# SCH_595__2023-01-18.net
KiCad netlist of a schematic drawn in EasyEDA
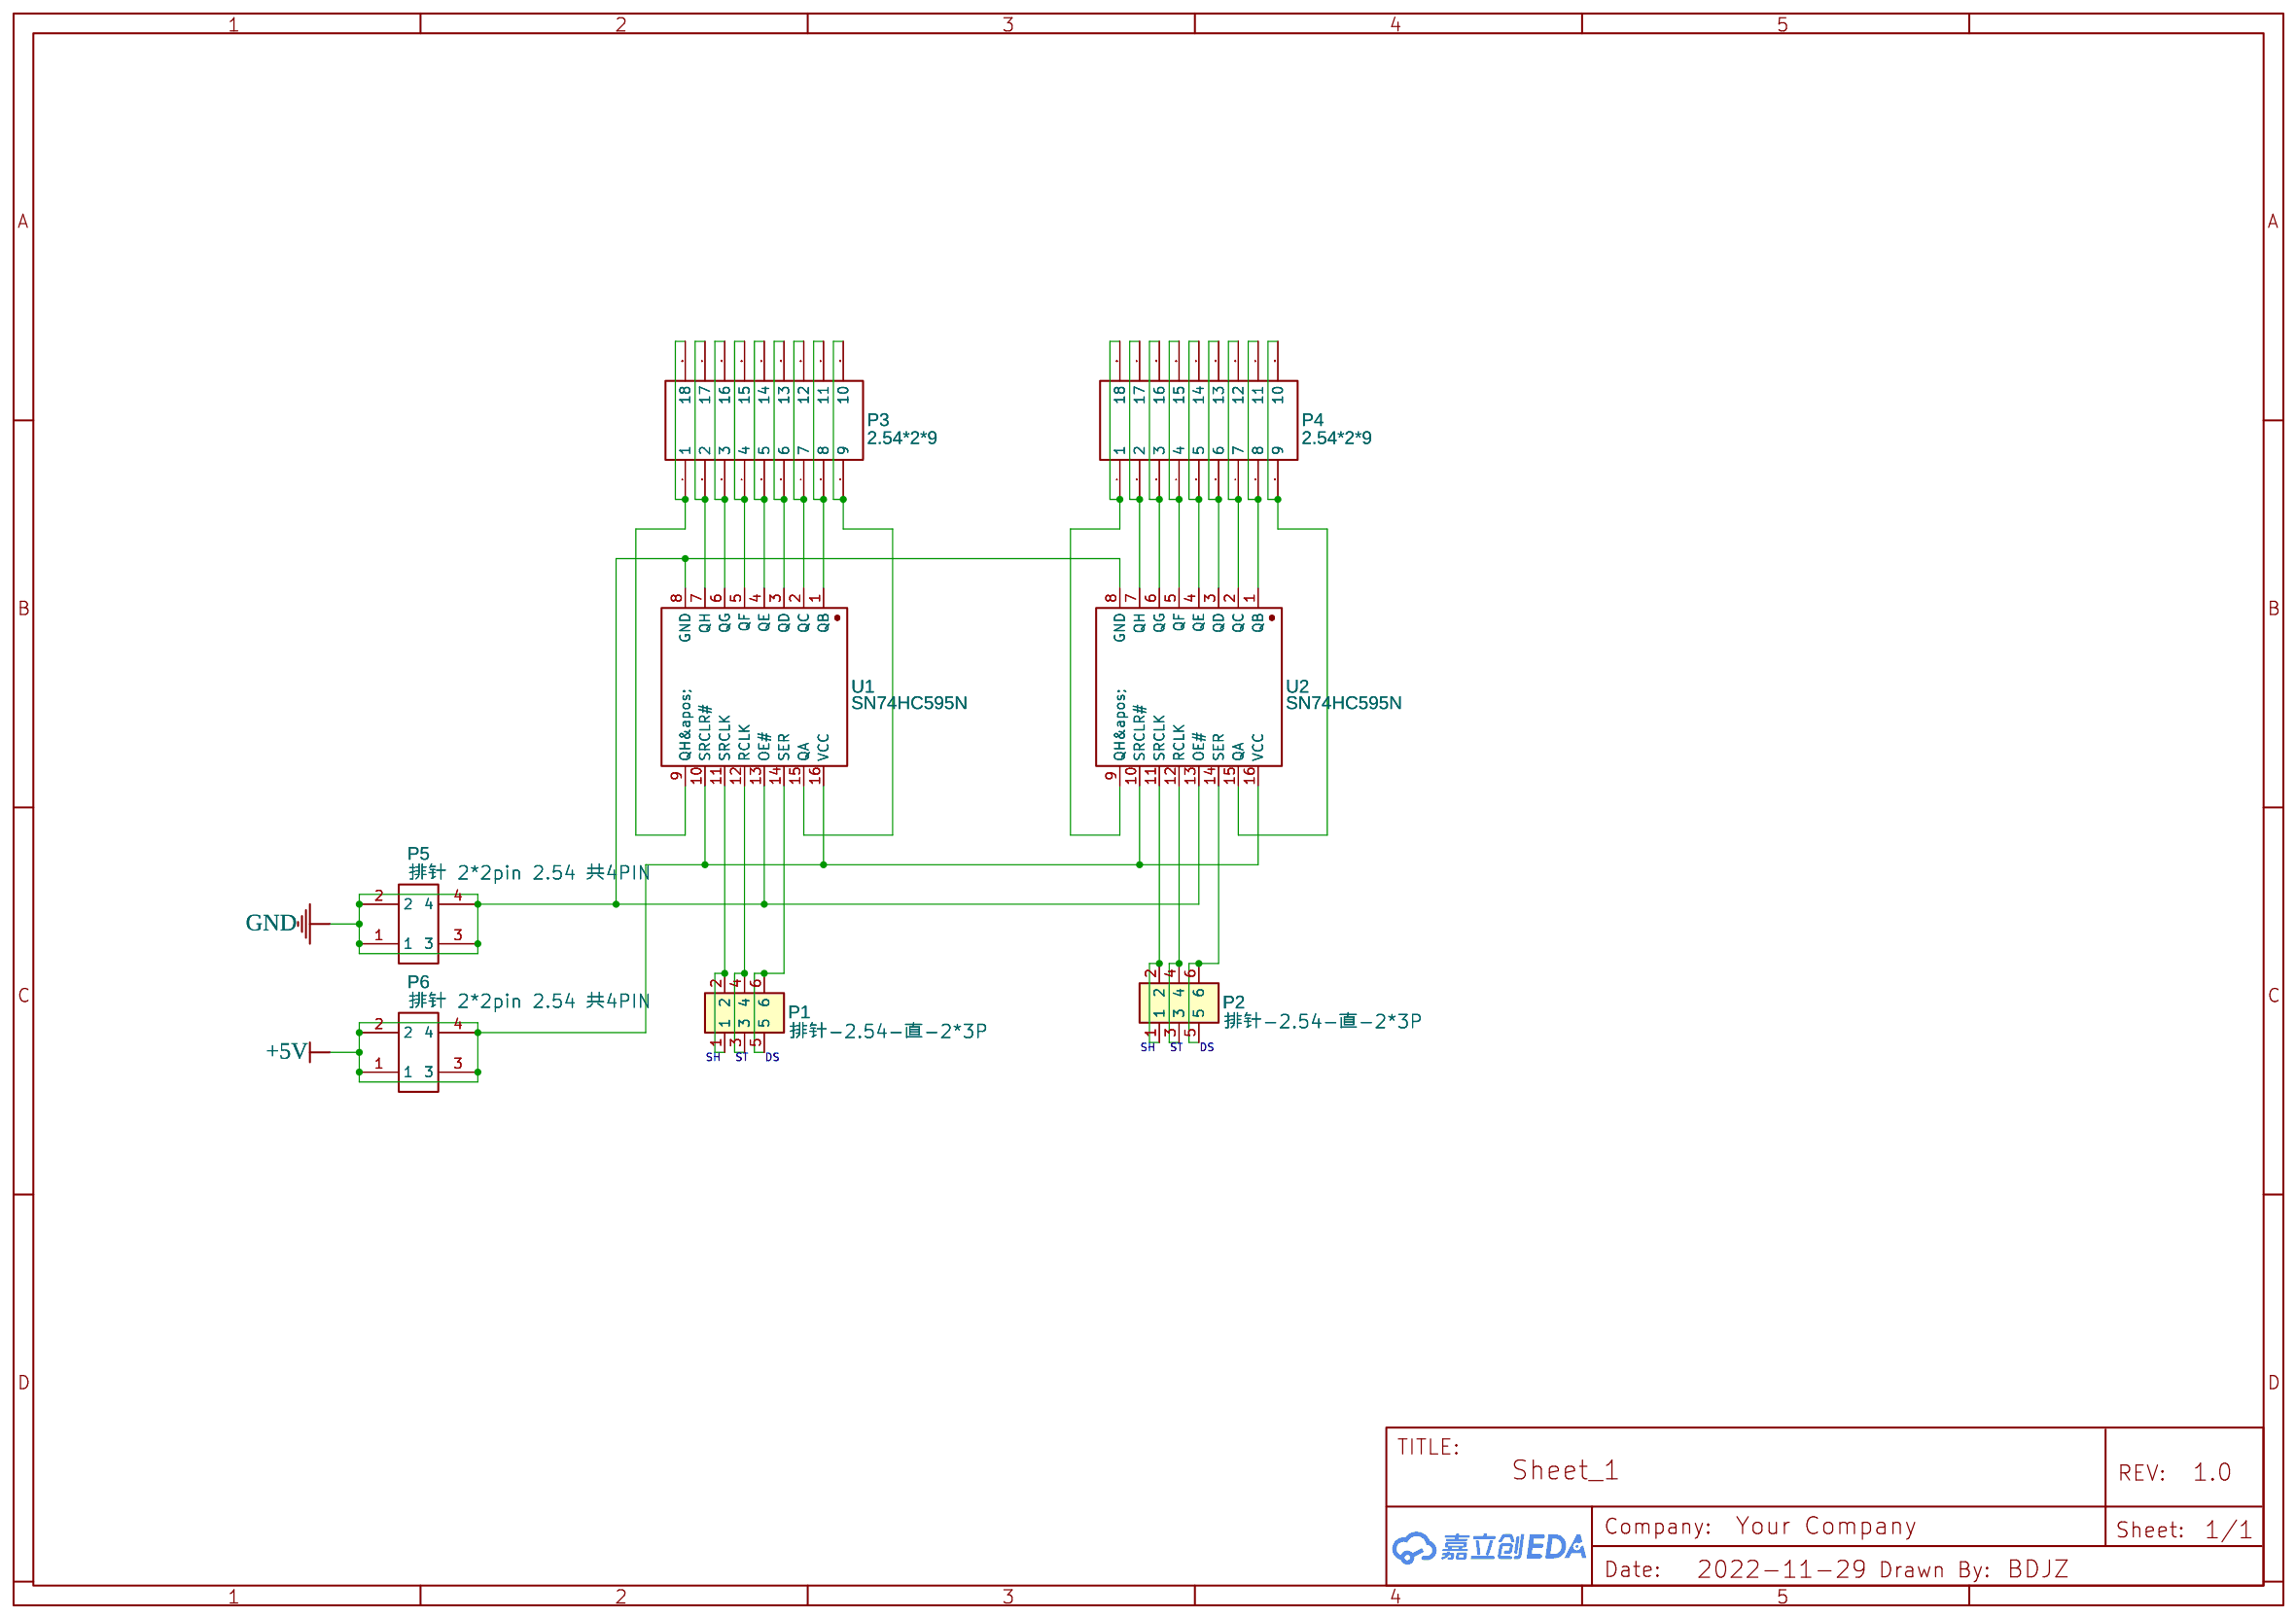
[diagram p0: schematic sheet]

(export (version "E")
  (design (tool "Eeschema 10.0.6"))
  (components
    (comp (ref "P1") (value "排针-2.54-直-2*3P") (libsource (lib "") (part "排针-2.54-直-2*3P")))
    (comp (ref "P2") (value "排针-2.54-直-2*3P") (libsource (lib "") (part "排针-2.54-直-2*3P")))
    (comp (ref "P3")
      (value "2.54*2*9")
      (fields (field (name "BOM_Supplier Part") "C115247"))
      (libsource (lib "") (part "2.54*2*9"))
    )
    (comp (ref "P4")
      (value "2.54*2*9")
      (fields (field (name "BOM_Supplier Part") "C115247"))
      (libsource (lib "") (part "2.54*2*9"))
    )
    (comp (ref "P5") (value "排针 2*2pin 2.54 共4PIN") (libsource (lib "") (part "排针 2*2pin 2.54 共4PIN")))
    (comp (ref "P6") (value "排针 2*2pin 2.54 共4PIN") (libsource (lib "") (part "排针 2*2pin 2.54 共4PIN")))
    (comp (ref "U1")
      (value "SN74HC595N")
      (fields (field (name "BOM_Supplier Part") "C78711"))
      (libsource (lib "") (part "SN74HC595N"))
    )
    (comp (ref "U2")
      (value "SN74HC595N")
      (fields (field (name "BOM_Supplier Part") "C78711"))
      (libsource (lib "") (part "SN74HC595N"))
    )
  )
  (nets
    (net (code "1") (name "+5V") (class "Default")
      (node (ref "P6") (pin "1") (pinfunction "1_1") (pintype "unspecified"))
      (node (ref "P6") (pin "2") (pinfunction "2_2") (pintype "unspecified"))
      (node (ref "P6") (pin "3") (pinfunction "3_3") (pintype "unspecified"))
      (node (ref "P6") (pin "4") (pinfunction "4_4") (pintype "unspecified"))
      (node (ref "U1") (pin "10") (pinfunction "SRCLR#_10") (pintype "unspecified"))
      (node (ref "U1") (pin "16") (pinfunction "VCC_16") (pintype "unspecified"))
      (node (ref "U2") (pin "10") (pinfunction "SRCLR#_10") (pintype "unspecified"))
      (node (ref "U2") (pin "16") (pinfunction "VCC_16") (pintype "unspecified"))
    )
    (net (code "2") (name "GND") (class "Default")
      (node (ref "P5") (pin "1") (pinfunction "1_1") (pintype "unspecified"))
      (node (ref "P5") (pin "2") (pinfunction "2_2") (pintype "unspecified"))
      (node (ref "P5") (pin "3") (pinfunction "3_3") (pintype "unspecified"))
      (node (ref "P5") (pin "4") (pinfunction "4_4") (pintype "unspecified"))
      (node (ref "U1") (pin "13") (pinfunction "OE#_13") (pintype "unspecified"))
      (node (ref "U1") (pin "8") (pinfunction "GND_8") (pintype "unspecified"))
      (node (ref "U2") (pin "13") (pinfunction "OE#_13") (pintype "unspecified"))
      (node (ref "U2") (pin "8") (pinfunction "GND_8") (pintype "unspecified"))
    )
    (net (code "3") (name "Net-(U1-QA)") (class "Default")
      (node (ref "P3") (pin "10") (pinfunction "10_10") (pintype "unspecified"))
      (node (ref "P3") (pin "9") (pinfunction "9_9") (pintype "unspecified"))
      (node (ref "U1") (pin "15") (pinfunction "QA_15") (pintype "unspecified"))
    )
    (net (code "4") (name "Net-(U1-QB)") (class "Default")
      (node (ref "P3") (pin "11") (pinfunction "11_11") (pintype "unspecified"))
      (node (ref "P3") (pin "8") (pinfunction "8_8") (pintype "unspecified"))
      (node (ref "U1") (pin "1") (pinfunction "QB_1") (pintype "unspecified"))
    )
    (net (code "5") (name "Net-(U1-QC)") (class "Default")
      (node (ref "P3") (pin "12") (pinfunction "12_12") (pintype "unspecified"))
      (node (ref "P3") (pin "7") (pinfunction "7_7") (pintype "unspecified"))
      (node (ref "U1") (pin "2") (pinfunction "QC_2") (pintype "unspecified"))
    )
    (net (code "6") (name "Net-(U1-QD)") (class "Default")
      (node (ref "P3") (pin "13") (pinfunction "13_13") (pintype "unspecified"))
      (node (ref "P3") (pin "6") (pinfunction "6_6") (pintype "unspecified"))
      (node (ref "U1") (pin "3") (pinfunction "QD_3") (pintype "unspecified"))
    )
    (net (code "7") (name "Net-(U1-QE)") (class "Default")
      (node (ref "P3") (pin "14") (pinfunction "14_14") (pintype "unspecified"))
      (node (ref "P3") (pin "5") (pinfunction "5_5") (pintype "unspecified"))
      (node (ref "U1") (pin "4") (pinfunction "QE_4") (pintype "unspecified"))
    )
    (net (code "8") (name "Net-(U1-QF)") (class "Default")
      (node (ref "P3") (pin "15") (pinfunction "15_15") (pintype "unspecified"))
      (node (ref "P3") (pin "4") (pinfunction "4_4") (pintype "unspecified"))
      (node (ref "U1") (pin "5") (pinfunction "QF_5") (pintype "unspecified"))
    )
    (net (code "9") (name "Net-(U1-QG)") (class "Default")
      (node (ref "P3") (pin "16") (pinfunction "16_16") (pintype "unspecified"))
      (node (ref "P3") (pin "3") (pinfunction "3_3") (pintype "unspecified"))
      (node (ref "U1") (pin "6") (pinfunction "QG_6") (pintype "unspecified"))
    )
    (net (code "10") (name "Net-(U1-QH&apos;)") (class "Default")
      (node (ref "P3") (pin "1") (pinfunction "1_1") (pintype "unspecified"))
      (node (ref "P3") (pin "18") (pinfunction "18_18") (pintype "unspecified"))
      (node (ref "U1") (pin "9") (pinfunction "QH&apos;_9") (pintype "unspecified"))
    )
    (net (code "11") (name "Net-(U1-QH)") (class "Default")
      (node (ref "P3") (pin "17") (pinfunction "17_17") (pintype "unspecified"))
      (node (ref "P3") (pin "2") (pinfunction "2_2") (pintype "unspecified"))
      (node (ref "U1") (pin "7") (pinfunction "QH_7") (pintype "unspecified"))
    )
    (net (code "12") (name "Net-(U1-RCLK)") (class "Default")
      (node (ref "P1") (pin "3") (pinfunction "3_3") (pintype "unspecified"))
      (node (ref "P1") (pin "4") (pinfunction "4_4") (pintype "unspecified"))
      (node (ref "U1") (pin "12") (pinfunction "RCLK_12") (pintype "unspecified"))
    )
    (net (code "13") (name "Net-(U1-SER)") (class "Default")
      (node (ref "P1") (pin "5") (pinfunction "5_5") (pintype "unspecified"))
      (node (ref "P1") (pin "6") (pinfunction "6_6") (pintype "unspecified"))
      (node (ref "U1") (pin "14") (pinfunction "SER_14") (pintype "unspecified"))
    )
    (net (code "14") (name "Net-(U1-SRCLK)") (class "Default")
      (node (ref "P1") (pin "1") (pinfunction "1_1") (pintype "unspecified"))
      (node (ref "P1") (pin "2") (pinfunction "2_2") (pintype "unspecified"))
      (node (ref "U1") (pin "11") (pinfunction "SRCLK_11") (pintype "unspecified"))
    )
    (net (code "15") (name "Net-(U2-QA)") (class "Default")
      (node (ref "P4") (pin "10") (pinfunction "10_10") (pintype "unspecified"))
      (node (ref "P4") (pin "9") (pinfunction "9_9") (pintype "unspecified"))
      (node (ref "U2") (pin "15") (pinfunction "QA_15") (pintype "unspecified"))
    )
    (net (code "16") (name "Net-(U2-QB)") (class "Default")
      (node (ref "P4") (pin "11") (pinfunction "11_11") (pintype "unspecified"))
      (node (ref "P4") (pin "8") (pinfunction "8_8") (pintype "unspecified"))
      (node (ref "U2") (pin "1") (pinfunction "QB_1") (pintype "unspecified"))
    )
    (net (code "17") (name "Net-(U2-QC)") (class "Default")
      (node (ref "P4") (pin "12") (pinfunction "12_12") (pintype "unspecified"))
      (node (ref "P4") (pin "7") (pinfunction "7_7") (pintype "unspecified"))
      (node (ref "U2") (pin "2") (pinfunction "QC_2") (pintype "unspecified"))
    )
    (net (code "18") (name "Net-(U2-QD)") (class "Default")
      (node (ref "P4") (pin "13") (pinfunction "13_13") (pintype "unspecified"))
      (node (ref "P4") (pin "6") (pinfunction "6_6") (pintype "unspecified"))
      (node (ref "U2") (pin "3") (pinfunction "QD_3") (pintype "unspecified"))
    )
    (net (code "19") (name "Net-(U2-QE)") (class "Default")
      (node (ref "P4") (pin "14") (pinfunction "14_14") (pintype "unspecified"))
      (node (ref "P4") (pin "5") (pinfunction "5_5") (pintype "unspecified"))
      (node (ref "U2") (pin "4") (pinfunction "QE_4") (pintype "unspecified"))
    )
    (net (code "20") (name "Net-(U2-QF)") (class "Default")
      (node (ref "P4") (pin "15") (pinfunction "15_15") (pintype "unspecified"))
      (node (ref "P4") (pin "4") (pinfunction "4_4") (pintype "unspecified"))
      (node (ref "U2") (pin "5") (pinfunction "QF_5") (pintype "unspecified"))
    )
    (net (code "21") (name "Net-(U2-QG)") (class "Default")
      (node (ref "P4") (pin "16") (pinfunction "16_16") (pintype "unspecified"))
      (node (ref "P4") (pin "3") (pinfunction "3_3") (pintype "unspecified"))
      (node (ref "U2") (pin "6") (pinfunction "QG_6") (pintype "unspecified"))
    )
    (net (code "22") (name "Net-(U2-QH&apos;)") (class "Default")
      (node (ref "P4") (pin "1") (pinfunction "1_1") (pintype "unspecified"))
      (node (ref "P4") (pin "18") (pinfunction "18_18") (pintype "unspecified"))
      (node (ref "U2") (pin "9") (pinfunction "QH&apos;_9") (pintype "unspecified"))
    )
    (net (code "23") (name "Net-(U2-QH)") (class "Default")
      (node (ref "P4") (pin "17") (pinfunction "17_17") (pintype "unspecified"))
      (node (ref "P4") (pin "2") (pinfunction "2_2") (pintype "unspecified"))
      (node (ref "U2") (pin "7") (pinfunction "QH_7") (pintype "unspecified"))
    )
    (net (code "24") (name "Net-(U2-RCLK)") (class "Default")
      (node (ref "P2") (pin "3") (pinfunction "3_3") (pintype "unspecified"))
      (node (ref "P2") (pin "4") (pinfunction "4_4") (pintype "unspecified"))
      (node (ref "U2") (pin "12") (pinfunction "RCLK_12") (pintype "unspecified"))
    )
    (net (code "25") (name "Net-(U2-SER)") (class "Default")
      (node (ref "P2") (pin "5") (pinfunction "5_5") (pintype "unspecified"))
      (node (ref "P2") (pin "6") (pinfunction "6_6") (pintype "unspecified"))
      (node (ref "U2") (pin "14") (pinfunction "SER_14") (pintype "unspecified"))
    )
    (net (code "26") (name "Net-(U2-SRCLK)") (class "Default")
      (node (ref "P2") (pin "1") (pinfunction "1_1") (pintype "unspecified"))
      (node (ref "P2") (pin "2") (pinfunction "2_2") (pintype "unspecified"))
      (node (ref "U2") (pin "11") (pinfunction "SRCLK_11") (pintype "unspecified"))
    )
  )
)
